# Sheet1.net
KiCad netlist of a schematic drawn in Altium Designer
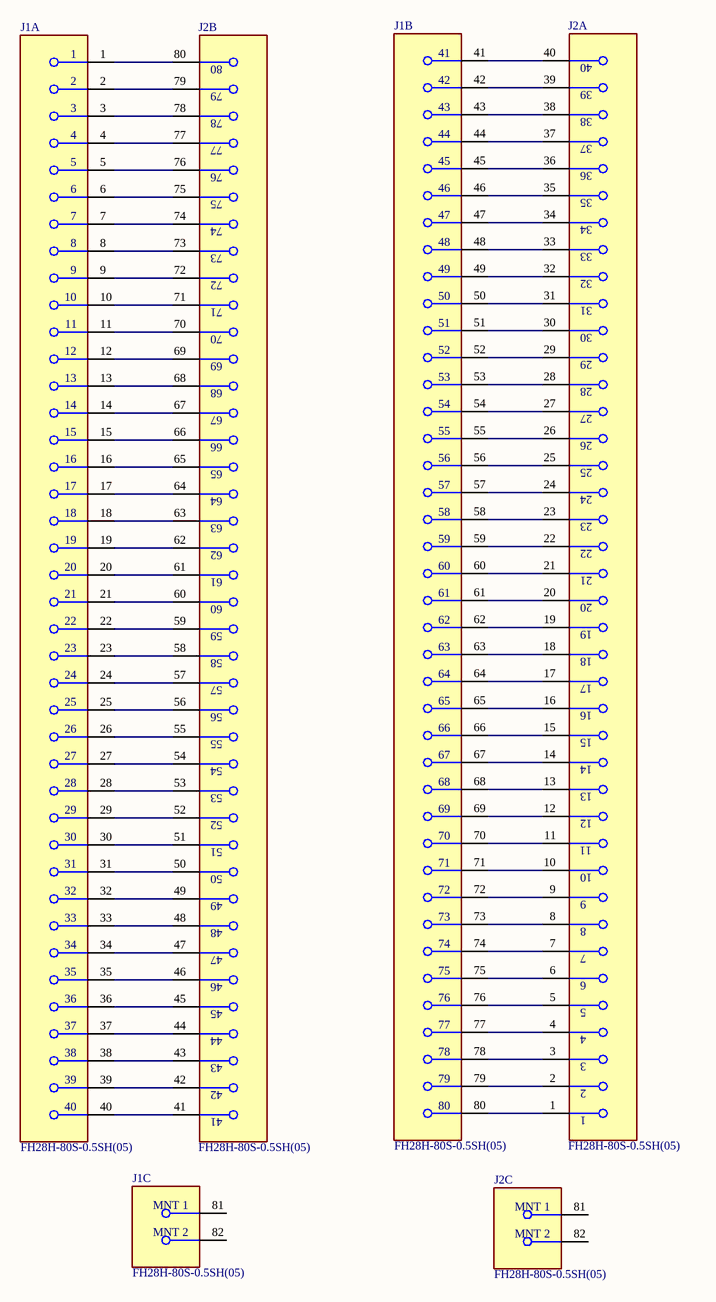
[diagram p0: Sheet1.SchDoc]

(export (version "E")
  (design (tool "Eeschema 10.0.6"))
  (components
    (comp (ref "J1")
      (value "FH28H-80S-0.5SH(05)")
      (footprint "FP-FH28H-80S-0_5SH_05-MFG")
      (description "CONN FFC BOTTOM 80POS 0.50MM R/A")
      (libsource (lib "") (part "08075b3669470a400ec152efcfe4938_1"))
    )
    (comp (ref "J2")
      (value "FH28H-80S-0.5SH(05)")
      (footprint "FP-FH28H-80S-0_5SH_05-MFG")
      (description "CONN FFC BOTTOM 80POS 0.50MM R/A")
      (libsource (lib "Altium Content Vault") (part "08075b3669470a400ec152efcfe4938"))
    )
  )
  (nets
    (net (code "1") (name "Net-(J1-Pad1)") (class "Default")
      (node (ref "J1") (pin "1") (pinfunction "1_1") (pintype "passive"))
      (node (ref "J2") (pin "80") (pinfunction "80_80") (pintype "passive"))
    )
    (net (code "2") (name "Net-(J1-Pad2)") (class "Default")
      (node (ref "J1") (pin "2") (pinfunction "2_2") (pintype "passive"))
      (node (ref "J2") (pin "79") (pinfunction "79_79") (pintype "passive"))
    )
    (net (code "3") (name "Net-(J1-Pad3)") (class "Default")
      (node (ref "J1") (pin "3") (pinfunction "3_3") (pintype "passive"))
      (node (ref "J2") (pin "78") (pinfunction "78_78") (pintype "passive"))
    )
    (net (code "4") (name "Net-(J1-Pad4)") (class "Default")
      (node (ref "J1") (pin "4") (pinfunction "4_4") (pintype "passive"))
      (node (ref "J2") (pin "77") (pinfunction "77_77") (pintype "passive"))
    )
    (net (code "5") (name "Net-(J1-Pad5)") (class "Default")
      (node (ref "J1") (pin "5") (pinfunction "5_5") (pintype "passive"))
      (node (ref "J2") (pin "76") (pinfunction "76_76") (pintype "passive"))
    )
    (net (code "6") (name "Net-(J1-Pad6)") (class "Default")
      (node (ref "J1") (pin "6") (pinfunction "6_6") (pintype "passive"))
      (node (ref "J2") (pin "75") (pinfunction "75_75") (pintype "passive"))
    )
    (net (code "7") (name "Net-(J1-Pad7)") (class "Default")
      (node (ref "J1") (pin "7") (pinfunction "7_7") (pintype "passive"))
      (node (ref "J2") (pin "74") (pinfunction "74_74") (pintype "passive"))
    )
    (net (code "8") (name "Net-(J1-Pad8)") (class "Default")
      (node (ref "J1") (pin "8") (pinfunction "8_8") (pintype "passive"))
      (node (ref "J2") (pin "73") (pinfunction "73_73") (pintype "passive"))
    )
    (net (code "9") (name "Net-(J1-Pad9)") (class "Default")
      (node (ref "J1") (pin "9") (pinfunction "9_9") (pintype "passive"))
      (node (ref "J2") (pin "72") (pinfunction "72_72") (pintype "passive"))
    )
    (net (code "10") (name "Net-(J1-Pad10)") (class "Default")
      (node (ref "J1") (pin "10") (pinfunction "10_10") (pintype "passive"))
      (node (ref "J2") (pin "71") (pinfunction "71_71") (pintype "passive"))
    )
    (net (code "11") (name "Net-(J1-Pad11)") (class "Default")
      (node (ref "J1") (pin "11") (pinfunction "11_11") (pintype "passive"))
      (node (ref "J2") (pin "70") (pinfunction "70_70") (pintype "passive"))
    )
    (net (code "12") (name "Net-(J1-Pad12)") (class "Default")
      (node (ref "J1") (pin "12") (pinfunction "12_12") (pintype "passive"))
      (node (ref "J2") (pin "69") (pinfunction "69_69") (pintype "passive"))
    )
    (net (code "13") (name "Net-(J1-Pad13)") (class "Default")
      (node (ref "J1") (pin "13") (pinfunction "13_13") (pintype "passive"))
      (node (ref "J2") (pin "68") (pinfunction "68_68") (pintype "passive"))
    )
    (net (code "14") (name "Net-(J1-Pad14)") (class "Default")
      (node (ref "J1") (pin "14") (pinfunction "14_14") (pintype "passive"))
      (node (ref "J2") (pin "67") (pinfunction "67_67") (pintype "passive"))
    )
    (net (code "15") (name "Net-(J1-Pad15)") (class "Default")
      (node (ref "J1") (pin "15") (pinfunction "15_15") (pintype "passive"))
      (node (ref "J2") (pin "66") (pinfunction "66_66") (pintype "passive"))
    )
    (net (code "16") (name "Net-(J1-Pad16)") (class "Default")
      (node (ref "J1") (pin "16") (pinfunction "16_16") (pintype "passive"))
      (node (ref "J2") (pin "65") (pinfunction "65_65") (pintype "passive"))
    )
    (net (code "17") (name "Net-(J1-Pad17)") (class "Default")
      (node (ref "J1") (pin "17") (pinfunction "17_17") (pintype "passive"))
      (node (ref "J2") (pin "64") (pinfunction "64_64") (pintype "passive"))
    )
    (net (code "18") (name "Net-(J1-Pad18)") (class "Default")
      (node (ref "J1") (pin "18") (pinfunction "18_18") (pintype "passive"))
      (node (ref "J2") (pin "63") (pinfunction "63_63") (pintype "passive"))
    )
    (net (code "19") (name "Net-(J1-Pad19)") (class "Default")
      (node (ref "J1") (pin "19") (pinfunction "19_19") (pintype "passive"))
      (node (ref "J2") (pin "62") (pinfunction "62_62") (pintype "passive"))
    )
    (net (code "20") (name "Net-(J1-Pad20)") (class "Default")
      (node (ref "J1") (pin "20") (pinfunction "20_20") (pintype "passive"))
      (node (ref "J2") (pin "61") (pinfunction "61_61") (pintype "passive"))
    )
    (net (code "21") (name "Net-(J1-Pad21)") (class "Default")
      (node (ref "J1") (pin "21") (pinfunction "21_21") (pintype "passive"))
      (node (ref "J2") (pin "60") (pinfunction "60_60") (pintype "passive"))
    )
    (net (code "22") (name "Net-(J1-Pad22)") (class "Default")
      (node (ref "J1") (pin "22") (pinfunction "22_22") (pintype "passive"))
      (node (ref "J2") (pin "59") (pinfunction "59_59") (pintype "passive"))
    )
    (net (code "23") (name "Net-(J1-Pad23)") (class "Default")
      (node (ref "J1") (pin "23") (pinfunction "23_23") (pintype "passive"))
      (node (ref "J2") (pin "58") (pinfunction "58_58") (pintype "passive"))
    )
    (net (code "24") (name "Net-(J1-Pad24)") (class "Default")
      (node (ref "J1") (pin "24") (pinfunction "24_24") (pintype "passive"))
      (node (ref "J2") (pin "57") (pinfunction "57_57") (pintype "passive"))
    )
    (net (code "25") (name "Net-(J1-Pad25)") (class "Default")
      (node (ref "J1") (pin "25") (pinfunction "25_25") (pintype "passive"))
      (node (ref "J2") (pin "56") (pinfunction "56_56") (pintype "passive"))
    )
    (net (code "26") (name "Net-(J1-Pad26)") (class "Default")
      (node (ref "J1") (pin "26") (pinfunction "26_26") (pintype "passive"))
      (node (ref "J2") (pin "55") (pinfunction "55_55") (pintype "passive"))
    )
    (net (code "27") (name "Net-(J1-Pad27)") (class "Default")
      (node (ref "J1") (pin "27") (pinfunction "27_27") (pintype "passive"))
      (node (ref "J2") (pin "54") (pinfunction "54_54") (pintype "passive"))
    )
    (net (code "28") (name "Net-(J1-Pad28)") (class "Default")
      (node (ref "J1") (pin "28") (pinfunction "28_28") (pintype "passive"))
      (node (ref "J2") (pin "53") (pinfunction "53_53") (pintype "passive"))
    )
    (net (code "29") (name "Net-(J1-Pad29)") (class "Default")
      (node (ref "J1") (pin "29") (pinfunction "29_29") (pintype "passive"))
      (node (ref "J2") (pin "52") (pinfunction "52_52") (pintype "passive"))
    )
    (net (code "30") (name "Net-(J1-Pad30)") (class "Default")
      (node (ref "J1") (pin "30") (pinfunction "30_30") (pintype "passive"))
      (node (ref "J2") (pin "51") (pinfunction "51_51") (pintype "passive"))
    )
    (net (code "31") (name "Net-(J1-Pad31)") (class "Default")
      (node (ref "J1") (pin "31") (pinfunction "31_31") (pintype "passive"))
      (node (ref "J2") (pin "50") (pinfunction "50_50") (pintype "passive"))
    )
    (net (code "32") (name "Net-(J1-Pad32)") (class "Default")
      (node (ref "J1") (pin "32") (pinfunction "32_32") (pintype "passive"))
      (node (ref "J2") (pin "49") (pinfunction "49_49") (pintype "passive"))
    )
    (net (code "33") (name "Net-(J1-Pad33)") (class "Default")
      (node (ref "J1") (pin "33") (pinfunction "33_33") (pintype "passive"))
      (node (ref "J2") (pin "48") (pinfunction "48_48") (pintype "passive"))
    )
    (net (code "34") (name "Net-(J1-Pad34)") (class "Default")
      (node (ref "J1") (pin "34") (pinfunction "34_34") (pintype "passive"))
      (node (ref "J2") (pin "47") (pinfunction "47_47") (pintype "passive"))
    )
    (net (code "35") (name "Net-(J1-Pad35)") (class "Default")
      (node (ref "J1") (pin "35") (pinfunction "35_35") (pintype "passive"))
      (node (ref "J2") (pin "46") (pinfunction "46_46") (pintype "passive"))
    )
    (net (code "36") (name "Net-(J1-Pad36)") (class "Default")
      (node (ref "J1") (pin "36") (pinfunction "36_36") (pintype "passive"))
      (node (ref "J2") (pin "45") (pinfunction "45_45") (pintype "passive"))
    )
    (net (code "37") (name "Net-(J1-Pad37)") (class "Default")
      (node (ref "J1") (pin "37") (pinfunction "37_37") (pintype "passive"))
      (node (ref "J2") (pin "44") (pinfunction "44_44") (pintype "passive"))
    )
    (net (code "38") (name "Net-(J1-Pad38)") (class "Default")
      (node (ref "J1") (pin "38") (pinfunction "38_38") (pintype "passive"))
      (node (ref "J2") (pin "43") (pinfunction "43_43") (pintype "passive"))
    )
    (net (code "39") (name "Net-(J1-Pad39)") (class "Default")
      (node (ref "J1") (pin "39") (pinfunction "39_39") (pintype "passive"))
      (node (ref "J2") (pin "42") (pinfunction "42_42") (pintype "passive"))
    )
    (net (code "40") (name "Net-(J1-Pad40)") (class "Default")
      (node (ref "J1") (pin "40") (pinfunction "40_40") (pintype "passive"))
      (node (ref "J2") (pin "41") (pinfunction "41_41") (pintype "passive"))
    )
    (net (code "41") (name "Net-(J1-Pad41)") (class "Default")
      (node (ref "J1") (pin "41") (pinfunction "41_41") (pintype "passive"))
      (node (ref "J2") (pin "40") (pinfunction "40_40") (pintype "passive"))
    )
    (net (code "42") (name "Net-(J1-Pad42)") (class "Default")
      (node (ref "J1") (pin "42") (pinfunction "42_42") (pintype "passive"))
      (node (ref "J2") (pin "39") (pinfunction "39_39") (pintype "passive"))
    )
    (net (code "43") (name "Net-(J1-Pad43)") (class "Default")
      (node (ref "J1") (pin "43") (pinfunction "43_43") (pintype "passive"))
      (node (ref "J2") (pin "38") (pinfunction "38_38") (pintype "passive"))
    )
    (net (code "44") (name "Net-(J1-Pad44)") (class "Default")
      (node (ref "J1") (pin "44") (pinfunction "44_44") (pintype "passive"))
      (node (ref "J2") (pin "37") (pinfunction "37_37") (pintype "passive"))
    )
    (net (code "45") (name "Net-(J1-Pad45)") (class "Default")
      (node (ref "J1") (pin "45") (pinfunction "45_45") (pintype "passive"))
      (node (ref "J2") (pin "36") (pinfunction "36_36") (pintype "passive"))
    )
    (net (code "46") (name "Net-(J1-Pad46)") (class "Default")
      (node (ref "J1") (pin "46") (pinfunction "46_46") (pintype "passive"))
      (node (ref "J2") (pin "35") (pinfunction "35_35") (pintype "passive"))
    )
    (net (code "47") (name "Net-(J1-Pad47)") (class "Default")
      (node (ref "J1") (pin "47") (pinfunction "47_47") (pintype "passive"))
      (node (ref "J2") (pin "34") (pinfunction "34_34") (pintype "passive"))
    )
    (net (code "48") (name "Net-(J1-Pad48)") (class "Default")
      (node (ref "J1") (pin "48") (pinfunction "48_48") (pintype "passive"))
      (node (ref "J2") (pin "33") (pinfunction "33_33") (pintype "passive"))
    )
    (net (code "49") (name "Net-(J1-Pad49)") (class "Default")
      (node (ref "J1") (pin "49") (pinfunction "49_49") (pintype "passive"))
      (node (ref "J2") (pin "32") (pinfunction "32_32") (pintype "passive"))
    )
    (net (code "50") (name "Net-(J1-Pad50)") (class "Default")
      (node (ref "J1") (pin "50") (pinfunction "50_50") (pintype "passive"))
      (node (ref "J2") (pin "31") (pinfunction "31_31") (pintype "passive"))
    )
    (net (code "51") (name "Net-(J1-Pad51)") (class "Default")
      (node (ref "J1") (pin "51") (pinfunction "51_51") (pintype "passive"))
      (node (ref "J2") (pin "30") (pinfunction "30_30") (pintype "passive"))
    )
    (net (code "52") (name "Net-(J1-Pad52)") (class "Default")
      (node (ref "J1") (pin "52") (pinfunction "52_52") (pintype "passive"))
      (node (ref "J2") (pin "29") (pinfunction "29_29") (pintype "passive"))
    )
    (net (code "53") (name "Net-(J1-Pad53)") (class "Default")
      (node (ref "J1") (pin "53") (pinfunction "53_53") (pintype "passive"))
      (node (ref "J2") (pin "28") (pinfunction "28_28") (pintype "passive"))
    )
    (net (code "54") (name "Net-(J1-Pad54)") (class "Default")
      (node (ref "J1") (pin "54") (pinfunction "54_54") (pintype "passive"))
      (node (ref "J2") (pin "27") (pinfunction "27_27") (pintype "passive"))
    )
    (net (code "55") (name "Net-(J1-Pad55)") (class "Default")
      (node (ref "J1") (pin "55") (pinfunction "55_55") (pintype "passive"))
      (node (ref "J2") (pin "26") (pinfunction "26_26") (pintype "passive"))
    )
    (net (code "56") (name "Net-(J1-Pad56)") (class "Default")
      (node (ref "J1") (pin "56") (pinfunction "56_56") (pintype "passive"))
      (node (ref "J2") (pin "25") (pinfunction "25_25") (pintype "passive"))
    )
    (net (code "57") (name "Net-(J1-Pad57)") (class "Default")
      (node (ref "J1") (pin "57") (pinfunction "57_57") (pintype "passive"))
      (node (ref "J2") (pin "24") (pinfunction "24_24") (pintype "passive"))
    )
    (net (code "58") (name "Net-(J1-Pad58)") (class "Default")
      (node (ref "J1") (pin "58") (pinfunction "58_58") (pintype "passive"))
      (node (ref "J2") (pin "23") (pinfunction "23_23") (pintype "passive"))
    )
    (net (code "59") (name "Net-(J1-Pad59)") (class "Default")
      (node (ref "J1") (pin "59") (pinfunction "59_59") (pintype "passive"))
      (node (ref "J2") (pin "22") (pinfunction "22_22") (pintype "passive"))
    )
    (net (code "60") (name "Net-(J1-Pad60)") (class "Default")
      (node (ref "J1") (pin "60") (pinfunction "60_60") (pintype "passive"))
      (node (ref "J2") (pin "21") (pinfunction "21_21") (pintype "passive"))
    )
    (net (code "61") (name "Net-(J1-Pad61)") (class "Default")
      (node (ref "J1") (pin "61") (pinfunction "61_61") (pintype "passive"))
      (node (ref "J2") (pin "20") (pinfunction "20_20") (pintype "passive"))
    )
    (net (code "62") (name "Net-(J1-Pad62)") (class "Default")
      (node (ref "J1") (pin "62") (pinfunction "62_62") (pintype "passive"))
      (node (ref "J2") (pin "19") (pinfunction "19_19") (pintype "passive"))
    )
    (net (code "63") (name "Net-(J1-Pad63)") (class "Default")
      (node (ref "J1") (pin "63") (pinfunction "63_63") (pintype "passive"))
      (node (ref "J2") (pin "18") (pinfunction "18_18") (pintype "passive"))
    )
    (net (code "64") (name "Net-(J1-Pad64)") (class "Default")
      (node (ref "J1") (pin "64") (pinfunction "64_64") (pintype "passive"))
      (node (ref "J2") (pin "17") (pinfunction "17_17") (pintype "passive"))
    )
    (net (code "65") (name "Net-(J1-Pad65)") (class "Default")
      (node (ref "J1") (pin "65") (pinfunction "65_65") (pintype "passive"))
      (node (ref "J2") (pin "16") (pinfunction "16_16") (pintype "passive"))
    )
    (net (code "66") (name "Net-(J1-Pad66)") (class "Default")
      (node (ref "J1") (pin "66") (pinfunction "66_66") (pintype "passive"))
      (node (ref "J2") (pin "15") (pinfunction "15_15") (pintype "passive"))
    )
    (net (code "67") (name "Net-(J1-Pad67)") (class "Default")
      (node (ref "J1") (pin "67") (pinfunction "67_67") (pintype "passive"))
      (node (ref "J2") (pin "14") (pinfunction "14_14") (pintype "passive"))
    )
    (net (code "68") (name "Net-(J1-Pad68)") (class "Default")
      (node (ref "J1") (pin "68") (pinfunction "68_68") (pintype "passive"))
      (node (ref "J2") (pin "13") (pinfunction "13_13") (pintype "passive"))
    )
    (net (code "69") (name "Net-(J1-Pad69)") (class "Default")
      (node (ref "J1") (pin "69") (pinfunction "69_69") (pintype "passive"))
      (node (ref "J2") (pin "12") (pinfunction "12_12") (pintype "passive"))
    )
    (net (code "70") (name "Net-(J1-Pad70)") (class "Default")
      (node (ref "J1") (pin "70") (pinfunction "70_70") (pintype "passive"))
      (node (ref "J2") (pin "11") (pinfunction "11_11") (pintype "passive"))
    )
    (net (code "71") (name "Net-(J1-Pad71)") (class "Default")
      (node (ref "J1") (pin "71") (pinfunction "71_71") (pintype "passive"))
      (node (ref "J2") (pin "10") (pinfunction "10_10") (pintype "passive"))
    )
    (net (code "72") (name "Net-(J1-Pad72)") (class "Default")
      (node (ref "J1") (pin "72") (pinfunction "72_72") (pintype "passive"))
      (node (ref "J2") (pin "9") (pinfunction "9_9") (pintype "passive"))
    )
    (net (code "73") (name "Net-(J1-Pad73)") (class "Default")
      (node (ref "J1") (pin "73") (pinfunction "73_73") (pintype "passive"))
      (node (ref "J2") (pin "8") (pinfunction "8_8") (pintype "passive"))
    )
    (net (code "74") (name "Net-(J1-Pad74)") (class "Default")
      (node (ref "J1") (pin "74") (pinfunction "74_74") (pintype "passive"))
      (node (ref "J2") (pin "7") (pinfunction "7_7") (pintype "passive"))
    )
    (net (code "75") (name "Net-(J1-Pad75)") (class "Default")
      (node (ref "J1") (pin "75") (pinfunction "75_75") (pintype "passive"))
      (node (ref "J2") (pin "6") (pinfunction "6_6") (pintype "passive"))
    )
    (net (code "76") (name "Net-(J1-Pad76)") (class "Default")
      (node (ref "J1") (pin "76") (pinfunction "76_76") (pintype "passive"))
      (node (ref "J2") (pin "5") (pinfunction "5_5") (pintype "passive"))
    )
    (net (code "77") (name "Net-(J1-Pad77)") (class "Default")
      (node (ref "J1") (pin "77") (pinfunction "77_77") (pintype "passive"))
      (node (ref "J2") (pin "4") (pinfunction "4_4") (pintype "passive"))
    )
    (net (code "78") (name "Net-(J1-Pad78)") (class "Default")
      (node (ref "J1") (pin "78") (pinfunction "78_78") (pintype "passive"))
      (node (ref "J2") (pin "3") (pinfunction "3_3") (pintype "passive"))
    )
    (net (code "79") (name "Net-(J1-Pad79)") (class "Default")
      (node (ref "J1") (pin "79") (pinfunction "79_79") (pintype "passive"))
      (node (ref "J2") (pin "2") (pinfunction "2_2") (pintype "passive"))
    )
    (net (code "80") (name "Net-(J1-Pad80)") (class "Default")
      (node (ref "J1") (pin "80") (pinfunction "80_80") (pintype "passive"))
      (node (ref "J2") (pin "1") (pinfunction "1_1") (pintype "passive"))
    )
    (net (code "81") (name "unconnected-(J1C-MNT_1-Pad81)") (class "Default")
      (node (ref "J1") (pin "81") (pinfunction "MNT_1_81") (pintype "passive"))
    )
    (net (code "82") (name "unconnected-(J1C-MNT_2-Pad82)") (class "Default")
      (node (ref "J1") (pin "82") (pinfunction "MNT_2_82") (pintype "passive"))
    )
    (net (code "83") (name "unconnected-(J2C-MNT_1-Pad81)") (class "Default")
      (node (ref "J2") (pin "81") (pinfunction "MNT_1_81") (pintype "passive"))
    )
    (net (code "84") (name "unconnected-(J2C-MNT_2-Pad82)") (class "Default")
      (node (ref "J2") (pin "82") (pinfunction "MNT_2_82") (pintype "passive"))
    )
  )
)
